# TwelfthMan.net
KiCad netlist of a schematic drawn in Altium Designer
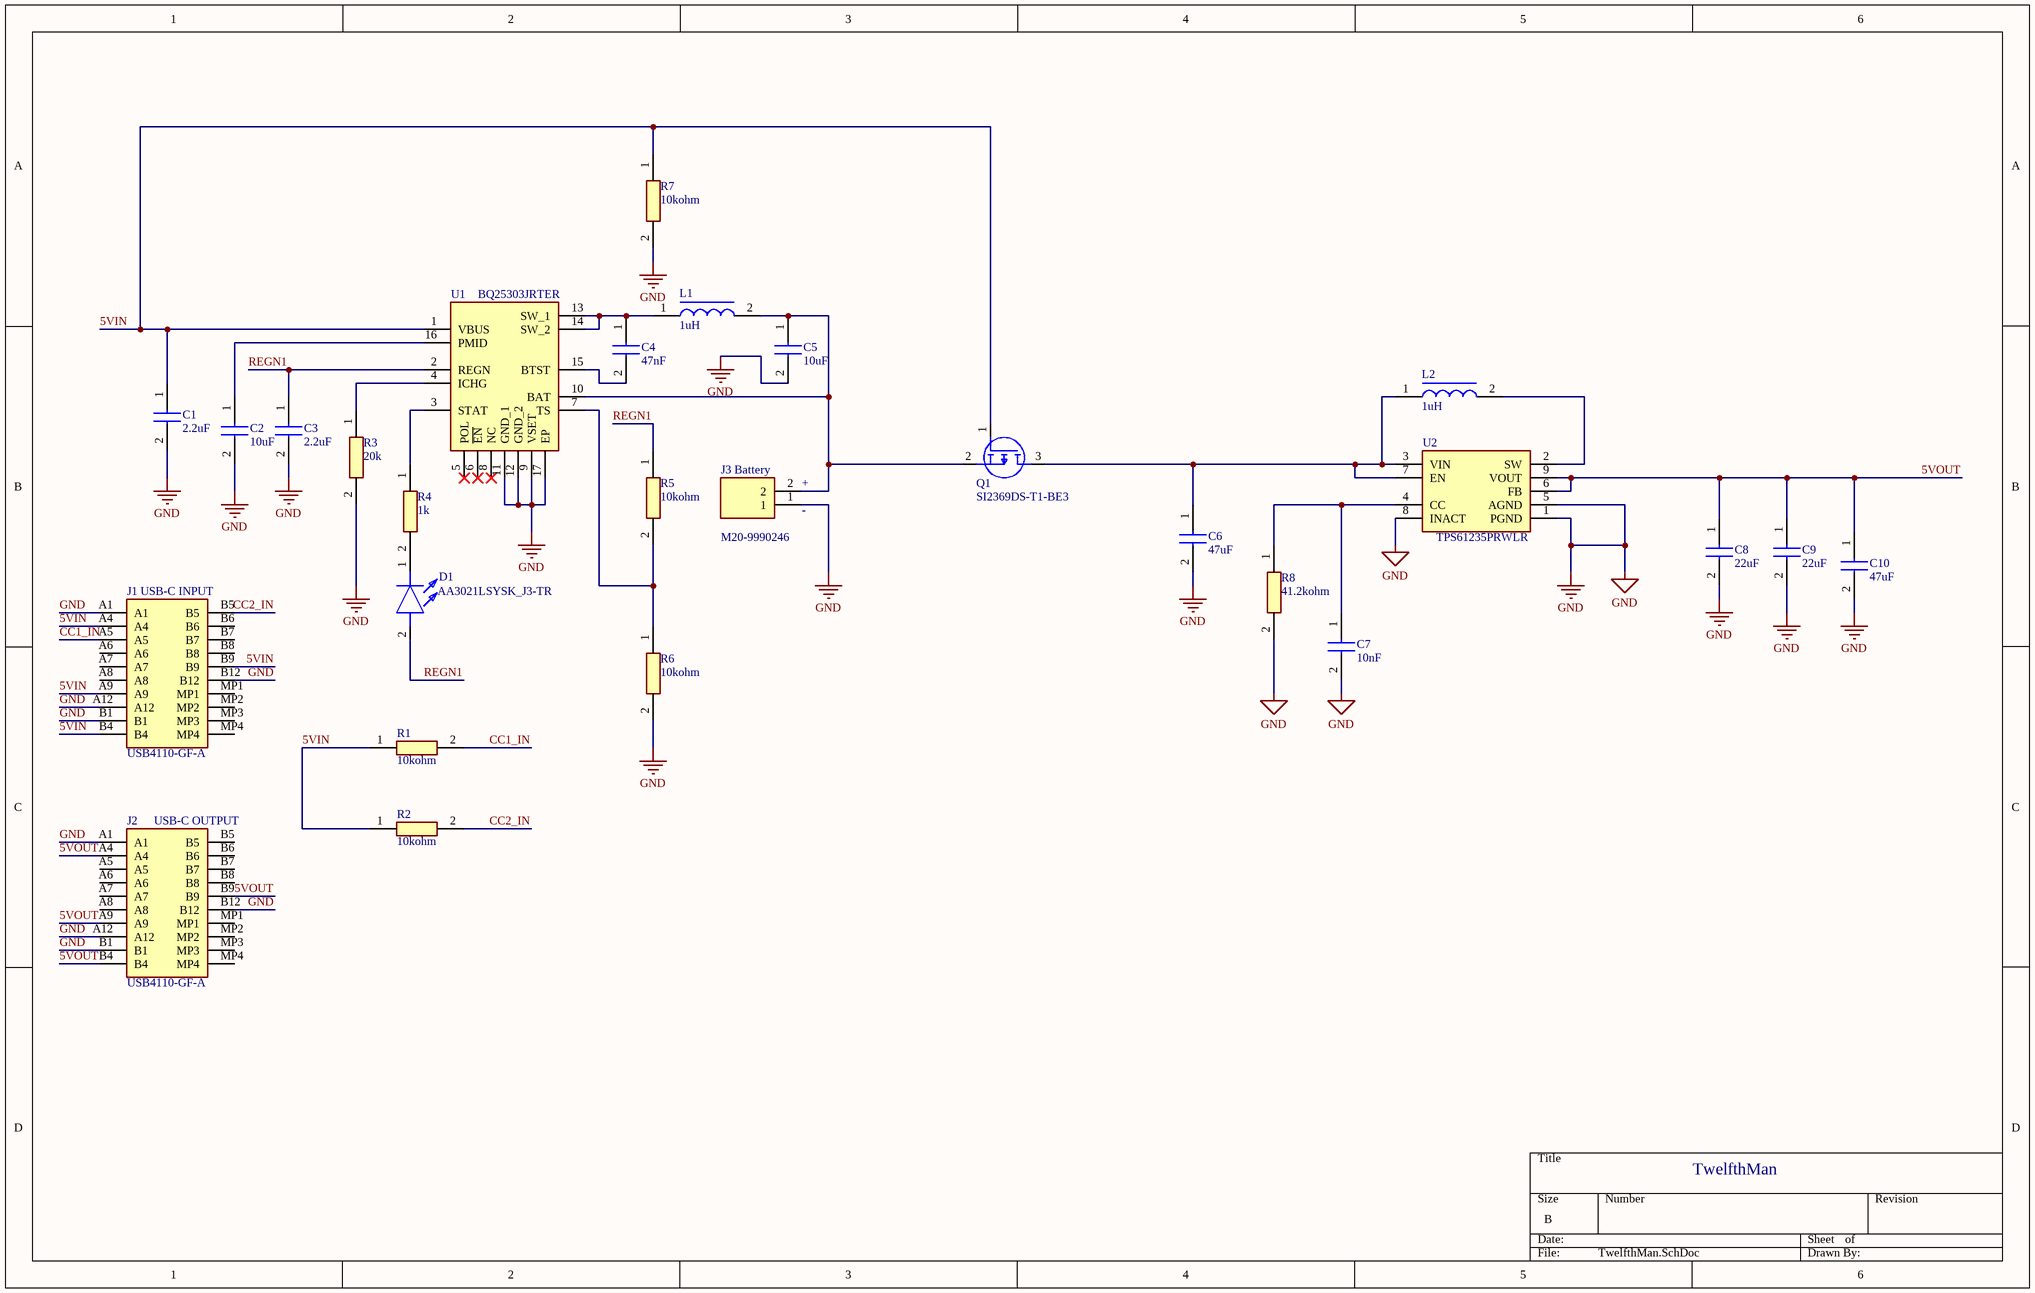
[diagram p0: TwelfthMan.SchDoc]

(export (version "E")
  (design (tool "Eeschema 10.0.6"))
  (components
    (comp (ref "C1")
      (value "2.2uF")
      (footprint "SamacSys:C3216_Commercial")
      (description "Capacitor - C3216X7R1V225K160AE")
      (fields
        (field (name "MANUFACTURER_PART_NUMBER") "C3216X7R1V225K160AE")
        (field (name "MOUSER PART NUMBER") "810-C3216X7R1V225KAE")
      )
      (libsource (lib "*") (part "C3216X7R1V225K160AE"))
    )
    (comp (ref "C2")
      (value "10uF")
      (footprint "SamacSys:CAPC3216X190N")
      (description "Capacitor - CNA5L1X7R1E106K160AE")
      (fields
        (field (name "MANUFACTURER_PART_NUMBER") "CNA5L1X7R1E106K160AE")
        (field (name "MOUSER PART NUMBER") "810-CNA5LX7R1E106K16")
      )
      (libsource (lib "*") (part "CNA5L1X7R1E106K160AE"))
    )
    (comp (ref "C3")
      (value "2.2uF")
      (footprint "SamacSys:C3216_Commercial")
      (description "Capacitor - C3216X7R1V225K160AE")
      (fields
        (field (name "MANUFACTURER_PART_NUMBER") "C3216X7R1V225K160AE")
        (field (name "MOUSER PART NUMBER") "810-C3216X7R1V225KAE")
      )
      (libsource (lib "*") (part "C3216X7R1V225K160AE"))
    )
    (comp (ref "C4")
      (value "47nF")
      (footprint "SamacSys:CAPC3216X175N")
      (description "Capacitor - C1206C561KDGACAUTO")
      (fields
        (field (name "MANUFACTURER_PART_NUMBER") "C1206C561KDGACAUTO")
        (field (name "MOUSER PART NUMBER") "80-C1206C561KDGAUTO")
      )
      (libsource (lib "*") (part "C1206C561KDGACAUTO"))
    )
    (comp (ref "C5")
      (value "10uF")
      (footprint "SamacSys:CAPC3216X190N")
      (description "Capacitor - CNA5L1X7R1E106K160AE")
      (fields
        (field (name "MANUFACTURER_PART_NUMBER") "CNA5L1X7R1E106K160AE")
        (field (name "MOUSER PART NUMBER") "810-CNA5LX7R1E106K16")
      )
      (libsource (lib "*") (part "CNA5L1X7R1E106K160AE"))
    )
    (comp (ref "C6")
      (value "47uF")
      (footprint "SamacSys:C2012_Commercial")
      (description "Capacitor - C2012X5R1A476M125AC")
      (fields
        (field (name "MANUFACTURER_PART_NUMBER") "C2012X5R1A476M125AC")
        (field (name "MOUSER PART NUMBER") "810-C2012X5R1A476M")
      )
      (libsource (lib "*") (part "C2012X5R1A476M125AC"))
    )
    (comp (ref "C7")
      (value "10nF")
      (footprint "SamacSys:C2012_Commercial")
      (description "Capacitor - C2012X5R2E103K125AA")
      (fields
        (field (name "MANUFACTURER_PART_NUMBER") "C2012X5R2E103K125AA")
        (field (name "MOUSER PART NUMBER") "810-C2012X5R2E103K1A")
      )
      (libsource (lib "*") (part "C2012X5R2E103K125AA"))
    )
    (comp (ref "C8")
      (value "22uF")
      (footprint "SamacSys:C2012_Commercial")
      (description "Capacitor - C2012X5R1A226M125AB")
      (fields
        (field (name "MANUFACTURER_PART_NUMBER") "C2012X5R1A226M125AB")
        (field (name "MOUSER PART NUMBER") "810-C2012X5R1A226M-3")
      )
      (libsource (lib "*") (part "C2012X5R1A226M125AB"))
    )
    (comp (ref "C9")
      (value "22uF")
      (footprint "SamacSys:C2012_Commercial")
      (description "Capacitor - C2012X5R1A226M125AB")
      (fields
        (field (name "MANUFACTURER_PART_NUMBER") "C2012X5R1A226M125AB")
        (field (name "MOUSER PART NUMBER") "810-C2012X5R1A226M-3")
      )
      (libsource (lib "*") (part "C2012X5R1A226M125AB"))
    )
    (comp (ref "C10")
      (value "47uF")
      (footprint "SamacSys:C2012_Commercial")
      (description "Capacitor - C2012X5R1A476M125AC")
      (fields
        (field (name "MANUFACTURER_PART_NUMBER") "C2012X5R1A476M125AC")
        (field (name "MOUSER PART NUMBER") "810-C2012X5R1A476M")
      )
      (libsource (lib "*") (part "C2012X5R1A476M125AC"))
    )
    (comp (ref "D1")
      (value "AA3021LSYSK_J3-TR")
      (footprint "SamacSys:AA3021LSYSKJ3TR")
      (description "LED-AA3021LSYSK_J3-TR")
      (fields
        (field (name "MANUFACTURER_PART_NUMBER") "AA3021LSYSK/J3-TR")
        (field (name "MOUSER PART NUMBER") "604-AA3021LSYSK/J3TR")
      )
      (libsource (lib "*") (part "AA3021LSYSK_J3-TR"))
    )
    (comp (ref "J1")
      (value "USB4110-GF-A")
      (footprint "SamacSys:USB4110GFA")
      (description "Connector")
      (fields (field (name "MOUSER PART NUMBER") "640-USB4110-GF-A"))
      (libsource (lib "*") (part "USB4110-GF-A"))
    )
    (comp (ref "J2")
      (value "USB4110-GF-A")
      (footprint "SamacSys:USB4110GFA")
      (description "Connector")
      (fields (field (name "MOUSER PART NUMBER") "640-USB4110-GF-A"))
      (libsource (lib "*") (part "USB4110-GF-A"))
    )
    (comp (ref "J3")
      (value "M20-9990246")
      (footprint "SamacSys:HDRV2W66P0X254_1X2_508X254X874P")
      (description "Connector")
      (fields (field (name "MOUSER PART NUMBER") "855-M20-9990246"))
      (libsource (lib "*") (part "M20-9990246"))
    )
    (comp (ref "L1")
      (value "1uH")
      (footprint "SamacSys:SPM6530")
      (description "Inductor (FeSi Core) - SPM6530T-1R0M120")
      (fields
        (field (name "MANUFACTURER_PART_NUMBER") "SPM6530T-1R0M120")
        (field (name "MOUSER PART NUMBER") "810-SPM6530T-1R0M120")
      )
      (libsource (lib "*") (part "SPM6530T-1R0M120"))
    )
    (comp (ref "L2")
      (value "1uH")
      (footprint "SamacSys:SPM6530")
      (description "Inductor (FeSi Core) - SPM6530T-1R0M120")
      (fields
        (field (name "MANUFACTURER_PART_NUMBER") "SPM6530T-1R0M120")
        (field (name "MOUSER PART NUMBER") "810-SPM6530T-1R0M120")
      )
      (libsource (lib "*") (part "SPM6530T-1R0M120"))
    )
    (comp (ref "Q1")
      (value "SI2369DS-T1-BE3")
      (footprint "SamacSys:SOT95P237X112-3N")
      (description "MOSFET (P-Channel)")
      (fields (field (name "MOUSER PART NUMBER") "78-SI2369DS-T1-BE3"))
      (libsource (lib "*") (part "SI2369DS-T1-BE3"))
    )
    (comp (ref "R1")
      (value "10kohm")
      (footprint "SamacSys:RESC2012X60N")
      (description "Resistor - CHP0805-FX-1002ELF")
      (fields
        (field (name "MANUFACTURER_PART_NUMBER") "CHP0805-FX-1002ELF")
        (field (name "MOUSER PART NUMBER") "652-CHP0805FX1002ELF")
      )
      (libsource (lib "") (part "CHP0805-FX-1002ELF_1"))
    )
    (comp (ref "R2")
      (value "10kohm")
      (footprint "SamacSys:RESC2012X60N")
      (description "Resistor - CHP0805-FX-1002ELF")
      (fields
        (field (name "MANUFACTURER_PART_NUMBER") "CHP0805-FX-1002ELF")
        (field (name "MOUSER PART NUMBER") "652-CHP0805FX1002ELF")
      )
      (libsource (lib "") (part "CHP0805-FX-1002ELF_1"))
    )
    (comp (ref "R3")
      (value "20k")
      (footprint "SamacSys:RESC3216X65N")
      (description "Resistor - RCS120620K0FKEA")
      (fields
        (field (name "MANUFACTURER_PART_NUMBER") "RCS120620K0FKEA")
        (field (name "MOUSER PART NUMBER") "71-RCS120620K0FKEA")
      )
      (libsource (lib "*") (part "RCS120620K0FKEA"))
    )
    (comp (ref "R4")
      (value "1k")
      (footprint "SamacSys:RCC1206_e3")
      (description "Resistor - RCC12061K00FKEA")
      (fields
        (field (name "MANUFACTURER_PART_NUMBER") "RCC12061K00FKEA")
        (field (name "MOUSER PART NUMBER") "71-RCC12061K00FKEA")
      )
      (libsource (lib "*") (part "RCC12061K00FKEA"))
    )
    (comp (ref "R5")
      (value "10kohm")
      (footprint "SamacSys:RESC2012X60N")
      (description "Resistor - CHP0805-FX-1002ELF")
      (fields
        (field (name "MANUFACTURER_PART_NUMBER") "CHP0805-FX-1002ELF")
        (field (name "MOUSER PART NUMBER") "652-CHP0805FX1002ELF")
      )
      (libsource (lib "*") (part "CHP0805-FX-1002ELF"))
    )
    (comp (ref "R6")
      (value "10kohm")
      (footprint "SamacSys:RESC2012X60N")
      (description "Resistor - CHP0805-FX-1002ELF")
      (fields
        (field (name "MANUFACTURER_PART_NUMBER") "CHP0805-FX-1002ELF")
        (field (name "MOUSER PART NUMBER") "652-CHP0805FX1002ELF")
      )
      (libsource (lib "*") (part "CHP0805-FX-1002ELF"))
    )
    (comp (ref "R7")
      (value "10kohm")
      (footprint "SamacSys:RESC2012X60N")
      (description "Resistor - CHP0805-FX-1002ELF")
      (fields
        (field (name "MANUFACTURER_PART_NUMBER") "CHP0805-FX-1002ELF")
        (field (name "MOUSER PART NUMBER") "652-CHP0805FX1002ELF")
      )
      (libsource (lib "*") (part "CHP0805-FX-1002ELF"))
    )
    (comp (ref "R8")
      (value "41.2kohm")
      (footprint "SamacSys:RESC2012X65N")
      (description "Resistor - RN73C2A41K2BTDF")
      (fields
        (field (name "MANUFACTURER_PART_NUMBER") "RN73C2A41K2BTDF")
        (field (name "MOUSER PART NUMBER") "279-RN73CA-41.2K")
      )
      (libsource (lib "*") (part "RN73C2A41K2BTDF"))
    )
    (comp (ref "U1")
      (value "BQ25303JRTER")
      (footprint "SamacSys:QFN50P300X300X80-17N-D")
      (description "Integrated Circuit")
      (fields (field (name "MOUSER PART NUMBER") "595-BQ25303JRTER"))
      (libsource (lib "*") (part "BQ25303JRTER"))
    )
    (comp (ref "U2")
      (value "TPS61235PRWLR")
      (footprint "SamacSys:TPS61235PRWLT")
      (description "Integrated Circuit - TPS61235PRWLR")
      (fields (field (name "MOUSER PART NUMBER") "595-TPS61235PRWLR"))
      (libsource (lib "*") (part "TPS61235PRWLR"))
    )
  )
  (nets
    (net (code "1") (name "/5VIN") (class "Default")
      (node (ref "C1") (pin "1") (pinfunction "1_1") (pintype "passive"))
      (node (ref "J1") (pin "A4") (pinfunction "A4_A4") (pintype "passive"))
      (node (ref "J1") (pin "A9") (pinfunction "A9_A9") (pintype "passive"))
      (node (ref "J1") (pin "B4") (pinfunction "B4_B4") (pintype "passive"))
      (node (ref "J1") (pin "B9") (pinfunction "B9_B9") (pintype "passive"))
      (node (ref "Q1") (pin "1") (pinfunction "G_1") (pintype "passive"))
      (node (ref "R1") (pin "1") (pinfunction "1_1") (pintype "passive"))
      (node (ref "R2") (pin "1") (pinfunction "1_1") (pintype "passive"))
      (node (ref "R7") (pin "1") (pinfunction "1_1") (pintype "passive"))
      (node (ref "U1") (pin "1") (pinfunction "VBUS_1") (pintype "passive"))
    )
    (net (code "2") (name "/5VOUT") (class "Default")
      (node (ref "C10") (pin "1") (pinfunction "1_1") (pintype "passive"))
      (node (ref "C8") (pin "1") (pinfunction "1_1") (pintype "passive"))
      (node (ref "C9") (pin "1") (pinfunction "1_1") (pintype "passive"))
      (node (ref "J2") (pin "A4") (pinfunction "A4_A4") (pintype "passive"))
      (node (ref "J2") (pin "A9") (pinfunction "A9_A9") (pintype "passive"))
      (node (ref "J2") (pin "B4") (pinfunction "B4_B4") (pintype "passive"))
      (node (ref "J2") (pin "B9") (pinfunction "B9_B9") (pintype "passive"))
      (node (ref "U2") (pin "6") (pinfunction "FB_6") (pintype "passive"))
      (node (ref "U2") (pin "9") (pinfunction "VOUT_9") (pintype "passive"))
    )
    (net (code "3") (name "/CC1_IN") (class "Default")
      (node (ref "J1") (pin "A5") (pinfunction "A5_A5") (pintype "passive"))
      (node (ref "R1") (pin "2") (pinfunction "2_2") (pintype "passive"))
    )
    (net (code "4") (name "/CC2_IN") (class "Default")
      (node (ref "J1") (pin "B5") (pinfunction "B5_B5") (pintype "passive"))
      (node (ref "R2") (pin "2") (pinfunction "2_2") (pintype "passive"))
    )
    (net (code "5") (name "/REGN1") (class "Default")
      (node (ref "C3") (pin "1") (pinfunction "1_1") (pintype "passive"))
      (node (ref "D1") (pin "2") (pinfunction "A_2") (pintype "passive"))
      (node (ref "R5") (pin "1") (pinfunction "1_1") (pintype "passive"))
      (node (ref "U1") (pin "2") (pinfunction "REGN_2") (pintype "passive"))
    )
    (net (code "6") (name "GND") (class "Default")
      (node (ref "C1") (pin "2") (pinfunction "2_2") (pintype "passive"))
      (node (ref "C10") (pin "2") (pinfunction "2_2") (pintype "passive"))
      (node (ref "C2") (pin "2") (pinfunction "2_2") (pintype "passive"))
      (node (ref "C3") (pin "2") (pinfunction "2_2") (pintype "passive"))
      (node (ref "C5") (pin "2") (pinfunction "2_2") (pintype "passive"))
      (node (ref "C6") (pin "2") (pinfunction "2_2") (pintype "passive"))
      (node (ref "C7") (pin "2") (pinfunction "2_2") (pintype "passive"))
      (node (ref "C8") (pin "2") (pinfunction "2_2") (pintype "passive"))
      (node (ref "C9") (pin "2") (pinfunction "2_2") (pintype "passive"))
      (node (ref "J1") (pin "A1") (pinfunction "A1_A1") (pintype "passive"))
      (node (ref "J1") (pin "A12") (pinfunction "A12_A12") (pintype "passive"))
      (node (ref "J1") (pin "B1") (pinfunction "B1_B1") (pintype "passive"))
      (node (ref "J1") (pin "B12") (pinfunction "B12_B12") (pintype "passive"))
      (node (ref "J2") (pin "A1") (pinfunction "A1_A1") (pintype "passive"))
      (node (ref "J2") (pin "A12") (pinfunction "A12_A12") (pintype "passive"))
      (node (ref "J2") (pin "B1") (pinfunction "B1_B1") (pintype "passive"))
      (node (ref "J2") (pin "B12") (pinfunction "B12_B12") (pintype "passive"))
      (node (ref "J3") (pin "1") (pinfunction "1_1") (pintype "passive"))
      (node (ref "R3") (pin "2") (pinfunction "2_2") (pintype "passive"))
      (node (ref "R6") (pin "2") (pinfunction "2_2") (pintype "passive"))
      (node (ref "R7") (pin "2") (pinfunction "2_2") (pintype "passive"))
      (node (ref "R8") (pin "2") (pinfunction "2_2") (pintype "passive"))
      (node (ref "U1") (pin "11") (pinfunction "GND_1_11") (pintype "passive"))
      (node (ref "U1") (pin "12") (pinfunction "GND_2_12") (pintype "passive"))
      (node (ref "U1") (pin "17") (pinfunction "EP_17") (pintype "passive"))
      (node (ref "U1") (pin "9") (pinfunction "VSET_9") (pintype "passive"))
      (node (ref "U2") (pin "1") (pinfunction "PGND_1") (pintype "passive"))
      (node (ref "U2") (pin "5") (pinfunction "AGND_5") (pintype "passive"))
      (node (ref "U2") (pin "8") (pinfunction "INACT_8") (pintype "passive"))
    )
    (net (code "7") (name "Net-(D1-K)") (class "Default")
      (node (ref "D1") (pin "1") (pinfunction "K_1") (pintype "passive"))
      (node (ref "R4") (pin "2") (pinfunction "2_2") (pintype "passive"))
    )
    (net (code "8") (name "Net-(Q1-D)") (class "Default")
      (node (ref "C6") (pin "1") (pinfunction "1_1") (pintype "passive"))
      (node (ref "L2") (pin "1") (pinfunction "1_1") (pintype "passive"))
      (node (ref "Q1") (pin "3") (pinfunction "D_3") (pintype "passive"))
      (node (ref "U2") (pin "3") (pinfunction "VIN_3") (pintype "passive"))
      (node (ref "U2") (pin "7") (pinfunction "EN_7") (pintype "passive"))
    )
    (net (code "9") (name "Net-(Q1-S)") (class "Default")
      (node (ref "C5") (pin "1") (pinfunction "1_1") (pintype "passive"))
      (node (ref "J3") (pin "2") (pinfunction "2_2") (pintype "passive"))
      (node (ref "L1") (pin "2") (pinfunction "2_2") (pintype "passive"))
      (node (ref "Q1") (pin "2") (pinfunction "S_2") (pintype "passive"))
      (node (ref "U1") (pin "10") (pinfunction "BAT_10") (pintype "passive"))
    )
    (net (code "10") (name "Net-(U1-BTST)") (class "Default")
      (node (ref "C4") (pin "2") (pinfunction "2_2") (pintype "passive"))
      (node (ref "U1") (pin "15") (pinfunction "BTST_15") (pintype "passive"))
    )
    (net (code "11") (name "Net-(U1-ICHG)") (class "Default")
      (node (ref "R3") (pin "1") (pinfunction "1_1") (pintype "passive"))
      (node (ref "U1") (pin "4") (pinfunction "ICHG_4") (pintype "passive"))
    )
    (net (code "12") (name "Net-(U1-PMID)") (class "Default")
      (node (ref "C2") (pin "1") (pinfunction "1_1") (pintype "passive"))
      (node (ref "U1") (pin "16") (pinfunction "PMID_16") (pintype "passive"))
    )
    (net (code "13") (name "Net-(U1-STAT)") (class "Default")
      (node (ref "R4") (pin "1") (pinfunction "1_1") (pintype "passive"))
      (node (ref "U1") (pin "3") (pinfunction "STAT_3") (pintype "passive"))
    )
    (net (code "14") (name "Net-(U1-SW_1)") (class "Default")
      (node (ref "C4") (pin "1") (pinfunction "1_1") (pintype "passive"))
      (node (ref "L1") (pin "1") (pinfunction "1_1") (pintype "passive"))
      (node (ref "U1") (pin "13") (pinfunction "SW_1_13") (pintype "passive"))
      (node (ref "U1") (pin "14") (pinfunction "SW_2_14") (pintype "passive"))
    )
    (net (code "15") (name "Net-(U1-TS)") (class "Default")
      (node (ref "R5") (pin "2") (pinfunction "2_2") (pintype "passive"))
      (node (ref "R6") (pin "1") (pinfunction "1_1") (pintype "passive"))
      (node (ref "U1") (pin "7") (pinfunction "TS_7") (pintype "passive"))
    )
    (net (code "16") (name "Net-(U2-CC)") (class "Default")
      (node (ref "C7") (pin "1") (pinfunction "1_1") (pintype "passive"))
      (node (ref "R8") (pin "1") (pinfunction "1_1") (pintype "passive"))
      (node (ref "U2") (pin "4") (pinfunction "CC_4") (pintype "passive"))
    )
    (net (code "17") (name "Net-(U2-SW)") (class "Default")
      (node (ref "L2") (pin "2") (pinfunction "2_2") (pintype "passive"))
      (node (ref "U2") (pin "2") (pinfunction "SW_2") (pintype "passive"))
    )
    (net (code "18") (name "unconnected-(J1-PadA6)") (class "Default")
      (node (ref "J1") (pin "A6") (pinfunction "A6_A6") (pintype "passive"))
    )
    (net (code "19") (name "unconnected-(J1-PadA7)") (class "Default")
      (node (ref "J1") (pin "A7") (pinfunction "A7_A7") (pintype "passive"))
    )
    (net (code "20") (name "unconnected-(J1-PadA8)") (class "Default")
      (node (ref "J1") (pin "A8") (pinfunction "A8_A8") (pintype "passive"))
    )
    (net (code "21") (name "unconnected-(J1-PadB6)") (class "Default")
      (node (ref "J1") (pin "B6") (pinfunction "B6_B6") (pintype "passive"))
    )
    (net (code "22") (name "unconnected-(J1-PadB7)") (class "Default")
      (node (ref "J1") (pin "B7") (pinfunction "B7_B7") (pintype "passive"))
    )
    (net (code "23") (name "unconnected-(J1-PadB8)") (class "Default")
      (node (ref "J1") (pin "B8") (pinfunction "B8_B8") (pintype "passive"))
    )
    (net (code "24") (name "unconnected-(J1-PadMP1)") (class "Default")
      (node (ref "J1") (pin "MP1") (pinfunction "MP1_MP1") (pintype "passive"))
    )
    (net (code "25") (name "unconnected-(J1-PadMP2)") (class "Default")
      (node (ref "J1") (pin "MP2") (pinfunction "MP2_MP2") (pintype "passive"))
    )
    (net (code "26") (name "unconnected-(J1-PadMP3)") (class "Default")
      (node (ref "J1") (pin "MP3") (pinfunction "MP3_MP3") (pintype "passive"))
    )
    (net (code "27") (name "unconnected-(J1-PadMP4)") (class "Default")
      (node (ref "J1") (pin "MP4") (pinfunction "MP4_MP4") (pintype "passive"))
    )
    (net (code "28") (name "unconnected-(J2-PadA5)") (class "Default")
      (node (ref "J2") (pin "A5") (pinfunction "A5_A5") (pintype "passive"))
    )
    (net (code "29") (name "unconnected-(J2-PadA6)") (class "Default")
      (node (ref "J2") (pin "A6") (pinfunction "A6_A6") (pintype "passive"))
    )
    (net (code "30") (name "unconnected-(J2-PadA7)") (class "Default")
      (node (ref "J2") (pin "A7") (pinfunction "A7_A7") (pintype "passive"))
    )
    (net (code "31") (name "unconnected-(J2-PadA8)") (class "Default")
      (node (ref "J2") (pin "A8") (pinfunction "A8_A8") (pintype "passive"))
    )
    (net (code "32") (name "unconnected-(J2-PadB5)") (class "Default")
      (node (ref "J2") (pin "B5") (pinfunction "B5_B5") (pintype "passive"))
    )
    (net (code "33") (name "unconnected-(J2-PadB6)") (class "Default")
      (node (ref "J2") (pin "B6") (pinfunction "B6_B6") (pintype "passive"))
    )
    (net (code "34") (name "unconnected-(J2-PadB7)") (class "Default")
      (node (ref "J2") (pin "B7") (pinfunction "B7_B7") (pintype "passive"))
    )
    (net (code "35") (name "unconnected-(J2-PadB8)") (class "Default")
      (node (ref "J2") (pin "B8") (pinfunction "B8_B8") (pintype "passive"))
    )
    (net (code "36") (name "unconnected-(J2-PadMP1)") (class "Default")
      (node (ref "J2") (pin "MP1") (pinfunction "MP1_MP1") (pintype "passive"))
    )
    (net (code "37") (name "unconnected-(J2-PadMP2)") (class "Default")
      (node (ref "J2") (pin "MP2") (pinfunction "MP2_MP2") (pintype "passive"))
    )
    (net (code "38") (name "unconnected-(J2-PadMP3)") (class "Default")
      (node (ref "J2") (pin "MP3") (pinfunction "MP3_MP3") (pintype "passive"))
    )
    (net (code "39") (name "unconnected-(J2-PadMP4)") (class "Default")
      (node (ref "J2") (pin "MP4") (pinfunction "MP4_MP4") (pintype "passive"))
    )
    (net (code "40") (name "unconnected-(U1-NC-Pad8)") (class "Default")
      (node (ref "U1") (pin "8") (pinfunction "NC_8") (pintype "passive+no_connect"))
    )
    (net (code "41") (name "unconnected-(U1-POL-Pad5)") (class "Default")
      (node (ref "U1") (pin "5") (pinfunction "POL_5") (pintype "passive+no_connect"))
    )
    (net (code "42") (name "unconnected-(U1-~{EN}-Pad6)") (class "Default")
      (node (ref "U1") (pin "6") (pinfunction "~{EN}_6") (pintype "passive+no_connect"))
    )
  )
)
